# Power_schematic.net
KiCad netlist of a schematic drawn in Altium Designer
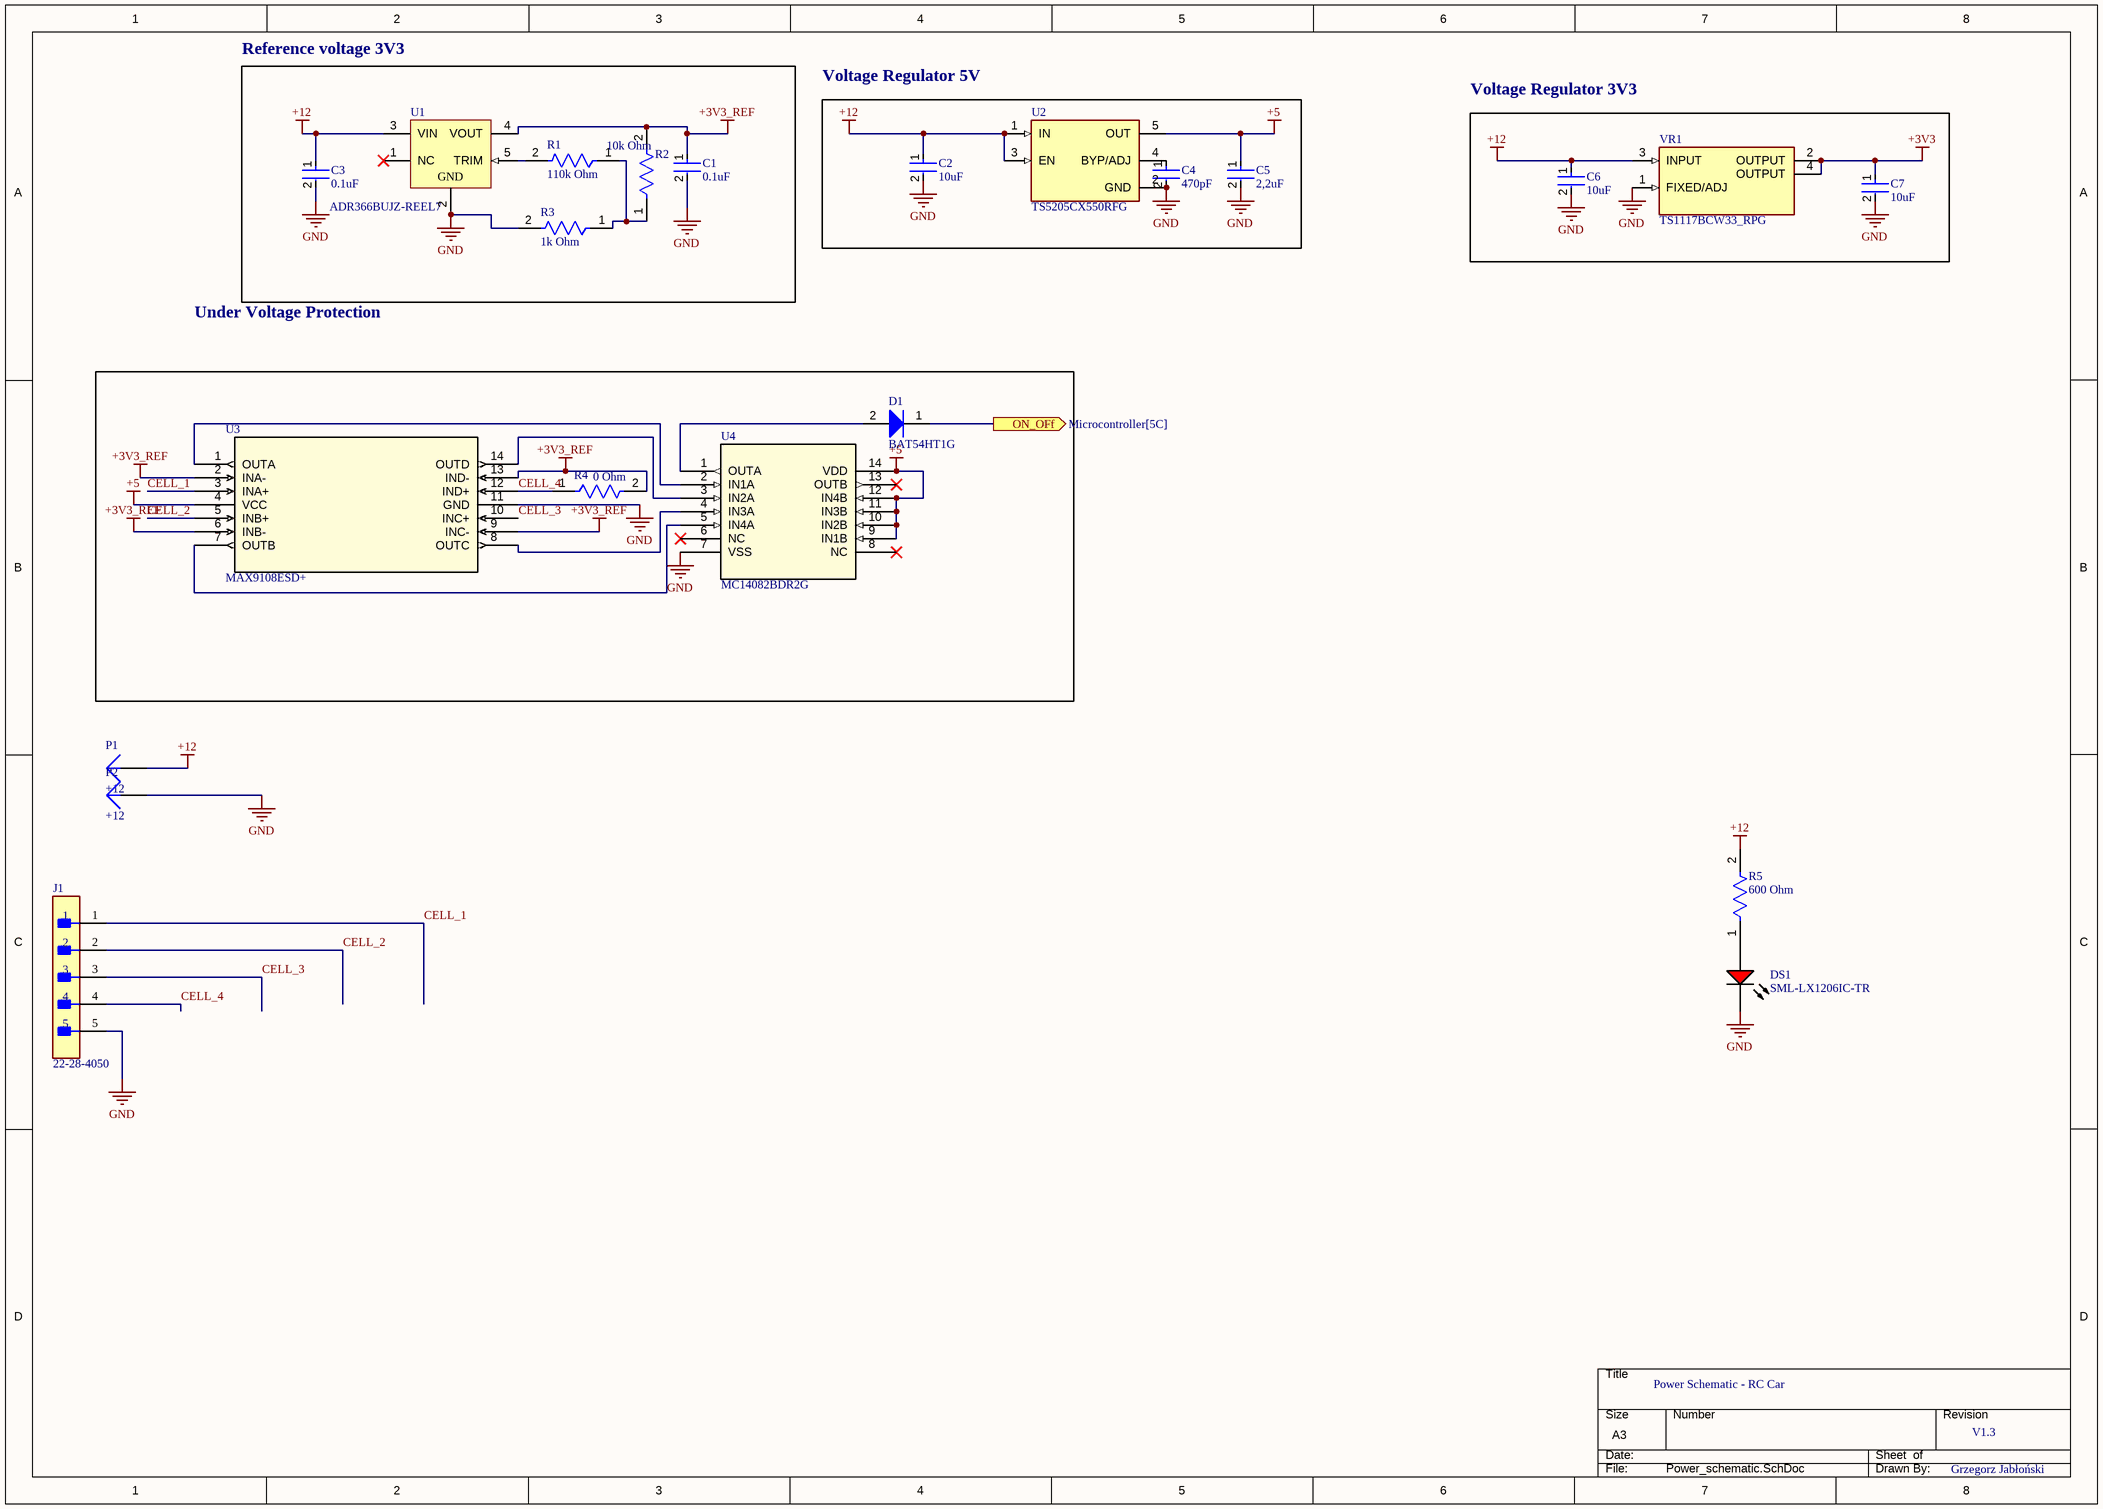
[diagram p0: Power_schematic.SchDoc]

(export (version "E")
  (design (tool "Eeschema 10.0.6"))
  (components
    (comp (ref "C1")
      (value "0.1uF")
      (footprint "FP-CC0805-0_85-MFG")
      (description "CAP CER 0.1UF 50V X7R 0805")
      (fields (field (name "TOLERANCE") "0.1") (field (name "MANUFACTURER PART NUMBER") "CC0805KRX7R9BB104"))
      (libsource (lib "Altium Content Vault") (part "11868f565c42a9108669ba33697ecf6"))
    )
    (comp (ref "C2")
      (value "10uF")
      (footprint "FP-CC0805-0_85-MFG")
      (description "CAP CER 0.1UF 50V X7R 0805")
      (fields (field (name "TOLERANCE") "0.1") (field (name "MANUFACTURER PART NUMBER") "CC0805KRX7R9BB104"))
      (libsource (lib "Altium Content Vault") (part "11868f565c42a9108669ba33697ecf6"))
    )
    (comp (ref "C3")
      (value "0.1uF")
      (footprint "FP-CC0805-0_85-MFG")
      (description "CAP CER 0.1UF 50V X7R 0805")
      (fields (field (name "TOLERANCE") "0.1") (field (name "MANUFACTURER PART NUMBER") "CC0805KRX7R9BB104"))
      (libsource (lib "Altium Content Vault") (part "11868f565c42a9108669ba33697ecf6"))
    )
    (comp (ref "C4")
      (value "470pF")
      (footprint "FP-CC0805-0_85-MFG")
      (description "CAP CER 0.1UF 50V X7R 0805")
      (fields (field (name "TOLERANCE") "0.1") (field (name "MANUFACTURER PART NUMBER") "CC0805KRX7R9BB104"))
      (libsource (lib "Altium Content Vault") (part "11868f565c42a9108669ba33697ecf6"))
    )
    (comp (ref "C5")
      (value "2,2uF")
      (footprint "FP-CC0805-0_85-MFG")
      (description "CAP CER 0.1UF 50V X7R 0805")
      (fields (field (name "TOLERANCE") "0.1") (field (name "MANUFACTURER PART NUMBER") "CC0805KRX7R9BB104"))
      (libsource (lib "Altium Content Vault") (part "11868f565c42a9108669ba33697ecf6"))
    )
    (comp (ref "C6")
      (value "10uF")
      (footprint "FP-CC0805-0_85-MFG")
      (description "CAP CER 0.1UF 50V X7R 0805")
      (fields (field (name "TOLERANCE") "0.1") (field (name "MANUFACTURER PART NUMBER") "CC0805KRX7R9BB104"))
      (libsource (lib "Altium Content Vault") (part "11868f565c42a9108669ba33697ecf6"))
    )
    (comp (ref "C7")
      (value "10uF")
      (footprint "FP-CC0805-0_85-MFG")
      (description "CAP CER 0.1UF 50V X7R 0805")
      (fields (field (name "TOLERANCE") "0.1") (field (name "MANUFACTURER PART NUMBER") "CC0805KRX7R9BB104"))
      (libsource (lib "Altium Content Vault") (part "11868f565c42a9108669ba33697ecf6"))
    )
    (comp (ref "D1")
      (value "BAT54HT1G")
      (footprint "ONSC-SOD-323-2-477-02_V")
      (description "Schottky Barrier Diode, 2-Pin SOD-323, Pb-Free, Tape and Reel")
      (fields (field (name "MANUFACTURER") "On Semiconductor"))
      (libsource (lib "Altium Content Vault") (part "ONSC-D-K1A2-2"))
    )
    (comp (ref "DS1")
      (value "SML-LX1206IC-TR")
      (footprint "LUMX-SML-LX1206IC_V")
      (description "LED Red, 65 mW, -40 to 85 degC, 2-Pin SMD, RoHS, Tape and Reel")
      (fields (field (name "MANUFACTURER") "Lumex"))
      (libsource (lib "Altium Content Vault") (part "LED-RED-AK-2"))
    )
    (comp (ref "J1")
      (value "22-28-4050")
      (footprint "FP-22-28-4050-MFG")
      (libsource (lib "Altium Content Vault") (part "bf93c07fd2649a848d0ec8585582aab"))
    )
    (comp (ref "P1")
      (value "+12")
      (footprint "PIN1")
      (description "Plug")
      (fields (field (name "PUBLISHER") "Altium Limited"))
      (libsource (lib "Miscellaneous Connectors") (part "Plug"))
    )
    (comp (ref "P2")
      (value "+12")
      (footprint "PIN1")
      (description "Plug")
      (fields (field (name "PUBLISHER") "Altium Limited"))
      (libsource (lib "Miscellaneous Connectors") (part "Plug"))
    )
    (comp (ref "R1")
      (value "110k Ohm")
      (footprint "FP-RMCF0805-MFG")
      (description "RES 0 OHM JUMPER 1/8W 0805")
      (libsource (lib "Altium Content Vault") (part "1029c3af85768c4190bb7ad29bc67b5"))
    )
    (comp (ref "R2")
      (value "10k Ohm")
      (footprint "FP-RMCF0805-MFG")
      (description "RES 0 OHM JUMPER 1/8W 0805")
      (libsource (lib "Altium Content Vault") (part "1029c3af85768c4190bb7ad29bc67b5"))
    )
    (comp (ref "R3")
      (value "1k Ohm")
      (footprint "FP-RMCF0805-MFG")
      (description "RES 0 OHM JUMPER 1/8W 0805")
      (libsource (lib "Altium Content Vault") (part "1029c3af85768c4190bb7ad29bc67b5"))
    )
    (comp (ref "R4")
      (value "0 Ohm")
      (footprint "FP-RMCF0805-MFG")
      (description "RES 0 OHM JUMPER 1/8W 0805")
      (libsource (lib "Altium Content Vault") (part "1029c3af85768c4190bb7ad29bc67b5"))
    )
    (comp (ref "R5")
      (value "600 Ohm")
      (footprint "FP-RMCF0805-MFG")
      (description "RES 0 OHM JUMPER 1/8W 0805")
      (libsource (lib "Altium Content Vault") (part "1029c3af85768c4190bb7ad29bc67b5"))
    )
    (comp (ref "U1")
      (value "ADR366BUJZ-REEL7")
      (footprint "ADI-UJ-5_L")
      (fields (field (name "MANUFACTURER") "Analog Devices"))
      (libsource (lib "Altium Content Vault") (part "ADI-ADR36X-UJ-5"))
    )
    (comp (ref "U2")
      (value "TS5205CX550RFG")
      (footprint "SOT95P270X125-5N")
      (fields (field (name "MF") "{'manufacturer': u'Taiwan Semiconductor Corporation'}"))
      (libsource (lib "TS5205CX550RFG") (part "TS5205CX550RFG"))
    )
    (comp (ref "U3")
      (value "MAX9108ESD+")
      (footprint "21-0041B_14")
      (description "No Description Available")
      (libsource (lib "MAX9108ESD&plus_") (part "MAX9108ESD+"))
    )
    (comp (ref "U4")
      (value "MC14082BDR2G")
      (footprint "SOIC-14_NB_ONS")
      (description "No Description Available")
      (libsource (lib "MC14082BDR2G") (part "MC14082BDR2G"))
    )
    (comp (ref "VR1")
      (value "TS1117BCW33_RPG")
      (footprint "VREG_TS1117BCW50_RPG")
      (fields (field (name "MP") "TS1117BCW50_RPG"))
      (libsource (lib "TS1117BCW50_RPG") (part "TS1117BCW50_RPG"))
    )
  )
  (nets
    (net (code "1") (name "+3V3") (class "Default")
      (node (ref "C7") (pin "1") (pinfunction "1_1") (pintype "passive"))
      (node (ref "VR1") (pin "2") (pinfunction "OUTPUT_2") (pintype "power_in"))
      (node (ref "VR1") (pin "4") (pinfunction "OUTPUT_4") (pintype "power_in"))
    )
    (net (code "2") (name "+3V3_REF") (class "Default")
      (node (ref "C1") (pin "1") (pinfunction "1_1") (pintype "passive"))
      (node (ref "R2") (pin "2") (pinfunction "2_2") (pintype "passive"))
      (node (ref "R4") (pin "2") (pinfunction "2_2") (pintype "passive"))
      (node (ref "U1") (pin "4") (pinfunction "VOUT_4") (pintype "power_in"))
      (node (ref "U3") (pin "13") (pinfunction "IND-_13") (pintype "input"))
      (node (ref "U3") (pin "2") (pinfunction "INA-_2") (pintype "input"))
      (node (ref "U3") (pin "6") (pinfunction "INB-_6") (pintype "input"))
      (node (ref "U3") (pin "9") (pinfunction "INC-_9") (pintype "input"))
    )
    (net (code "3") (name "+5") (class "Default")
      (node (ref "C5") (pin "1") (pinfunction "1_1") (pintype "passive"))
      (node (ref "U2") (pin "5") (pinfunction "OUT_5") (pintype "power_in"))
      (node (ref "U3") (pin "4") (pinfunction "VCC_4") (pintype "power_in"))
      (node (ref "U4") (pin "10") (pinfunction "IN2B_10") (pintype "input"))
      (node (ref "U4") (pin "11") (pinfunction "IN3B_11") (pintype "input"))
      (node (ref "U4") (pin "12") (pinfunction "IN4B_12") (pintype "input"))
      (node (ref "U4") (pin "14") (pinfunction "VDD_14") (pintype "power_in"))
      (node (ref "U4") (pin "9") (pinfunction "IN1B_9") (pintype "input"))
    )
    (net (code "4") (name "+12") (class "Default")
      (node (ref "C2") (pin "1") (pinfunction "1_1") (pintype "passive"))
      (node (ref "C3") (pin "1") (pinfunction "1_1") (pintype "passive"))
      (node (ref "C6") (pin "1") (pinfunction "1_1") (pintype "passive"))
      (node (ref "P1") (pin "1") (pinfunction "1_1") (pintype "passive"))
      (node (ref "R5") (pin "2") (pinfunction "2_2") (pintype "passive"))
      (node (ref "U1") (pin "3") (pinfunction "VIN_3") (pintype "power_in"))
      (node (ref "U2") (pin "1") (pinfunction "IN_1") (pintype "input"))
      (node (ref "U2") (pin "3") (pinfunction "EN_3") (pintype "input"))
      (node (ref "VR1") (pin "3") (pinfunction "INPUT_3") (pintype "input"))
    )
    (net (code "5") (name "/CELL_1") (class "Default")
      (node (ref "J1") (pin "1") (pinfunction "1_1") (pintype "passive"))
      (node (ref "U3") (pin "3") (pinfunction "INA+_3") (pintype "input"))
    )
    (net (code "6") (name "/CELL_2") (class "Default")
      (node (ref "J1") (pin "2") (pinfunction "2_2") (pintype "passive"))
      (node (ref "U3") (pin "5") (pinfunction "INB+_5") (pintype "input"))
    )
    (net (code "7") (name "/CELL_3") (class "Default")
      (node (ref "J1") (pin "3") (pinfunction "3_3") (pintype "passive"))
      (node (ref "U3") (pin "10") (pinfunction "INC+_10") (pintype "input"))
    )
    (net (code "8") (name "/CELL_4") (class "Default")
      (node (ref "J1") (pin "4") (pinfunction "4_4") (pintype "passive"))
      (node (ref "R4") (pin "1") (pinfunction "1_1") (pintype "passive"))
      (node (ref "U3") (pin "12") (pinfunction "IND+_12") (pintype "input"))
    )
    (net (code "9") (name "/ON_OFf") (class "Default")
      (node (ref "D1") (pin "1") (pinfunction "K_1") (pintype "passive"))
    )
    (net (code "10") (name "GND") (class "Default")
      (node (ref "C1") (pin "2") (pinfunction "2_2") (pintype "passive"))
      (node (ref "C2") (pin "2") (pinfunction "2_2") (pintype "passive"))
      (node (ref "C3") (pin "2") (pinfunction "2_2") (pintype "passive"))
      (node (ref "C4") (pin "2") (pinfunction "2_2") (pintype "passive"))
      (node (ref "C5") (pin "2") (pinfunction "2_2") (pintype "passive"))
      (node (ref "C6") (pin "2") (pinfunction "2_2") (pintype "passive"))
      (node (ref "C7") (pin "2") (pinfunction "2_2") (pintype "passive"))
      (node (ref "DS1") (pin "2") (pinfunction "K_2") (pintype "passive"))
      (node (ref "J1") (pin "5") (pinfunction "5_5") (pintype "passive"))
      (node (ref "P2") (pin "1") (pinfunction "1_1") (pintype "passive"))
      (node (ref "R3") (pin "2") (pinfunction "2_2") (pintype "passive"))
      (node (ref "U1") (pin "2") (pinfunction "GND_2") (pintype "power_in"))
      (node (ref "U2") (pin "2") (pinfunction "GND_2") (pintype "power_in"))
      (node (ref "U3") (pin "11") (pinfunction "GND_11") (pintype "power_in"))
      (node (ref "U4") (pin "7") (pinfunction "VSS_7") (pintype "power_in"))
      (node (ref "VR1") (pin "1") (pinfunction "FIXED/ADJ_1") (pintype "input"))
    )
    (net (code "11") (name "Net-(D1-A)") (class "Default")
      (node (ref "D1") (pin "2") (pinfunction "A_2") (pintype "passive"))
      (node (ref "U4") (pin "1") (pinfunction "OUTA_1") (pintype "output"))
    )
    (net (code "12") (name "Net-(DS1-A)") (class "Default")
      (node (ref "DS1") (pin "1") (pinfunction "A_1") (pintype "passive"))
      (node (ref "R5") (pin "1") (pinfunction "1_1") (pintype "passive"))
    )
    (net (code "13") (name "Net-(R1-Pad1)") (class "Default")
      (node (ref "R1") (pin "1") (pinfunction "1_1") (pintype "passive"))
      (node (ref "R2") (pin "1") (pinfunction "1_1") (pintype "passive"))
      (node (ref "R3") (pin "1") (pinfunction "1_1") (pintype "passive"))
    )
    (net (code "14") (name "Net-(U1-TRIM)") (class "Default")
      (node (ref "R1") (pin "2") (pinfunction "2_2") (pintype "passive"))
      (node (ref "U1") (pin "5") (pinfunction "TRIM_5") (pintype "input"))
    )
    (net (code "15") (name "Net-(U2-BYP{slash}ADJ)") (class "Default")
      (node (ref "C4") (pin "1") (pinfunction "1_1") (pintype "passive"))
      (node (ref "U2") (pin "4") (pinfunction "BYP/ADJ_4") (pintype "passive"))
    )
    (net (code "16") (name "Net-(U3-OUTA)") (class "Default")
      (node (ref "U3") (pin "1") (pinfunction "OUTA_1") (pintype "output"))
      (node (ref "U4") (pin "2") (pinfunction "IN1A_2") (pintype "input"))
    )
    (net (code "17") (name "Net-(U3-OUTB)") (class "Default")
      (node (ref "U3") (pin "7") (pinfunction "OUTB_7") (pintype "output"))
      (node (ref "U4") (pin "5") (pinfunction "IN4A_5") (pintype "input"))
    )
    (net (code "18") (name "Net-(U3-OUTC)") (class "Default")
      (node (ref "U3") (pin "8") (pinfunction "OUTC_8") (pintype "output"))
      (node (ref "U4") (pin "4") (pinfunction "IN3A_4") (pintype "input"))
    )
    (net (code "19") (name "Net-(U3-OUTD)") (class "Default")
      (node (ref "U3") (pin "14") (pinfunction "OUTD_14") (pintype "output"))
      (node (ref "U4") (pin "3") (pinfunction "IN2A_3") (pintype "input"))
    )
    (net (code "20") (name "unconnected-(U1-NC-Pad1)") (class "Default")
      (node (ref "U1") (pin "1") (pinfunction "NC_1") (pintype "passive+no_connect"))
    )
    (net (code "21") (name "unconnected-(U4-NC-Pad6)") (class "Default")
      (node (ref "U4") (pin "6") (pinfunction "NC_6") (pintype "passive+no_connect"))
    )
    (net (code "22") (name "unconnected-(U4-NC-Pad8)") (class "Default")
      (node (ref "U4") (pin "8") (pinfunction "NC_8") (pintype "passive+no_connect"))
    )
    (net (code "23") (name "unconnected-(U4-OUTB-Pad13)") (class "Default")
      (node (ref "U4") (pin "13") (pinfunction "OUTB_13") (pintype "output+no_connect"))
    )
  )
)
